# MCU.net
KiCad netlist of a schematic drawn in Altium Designer
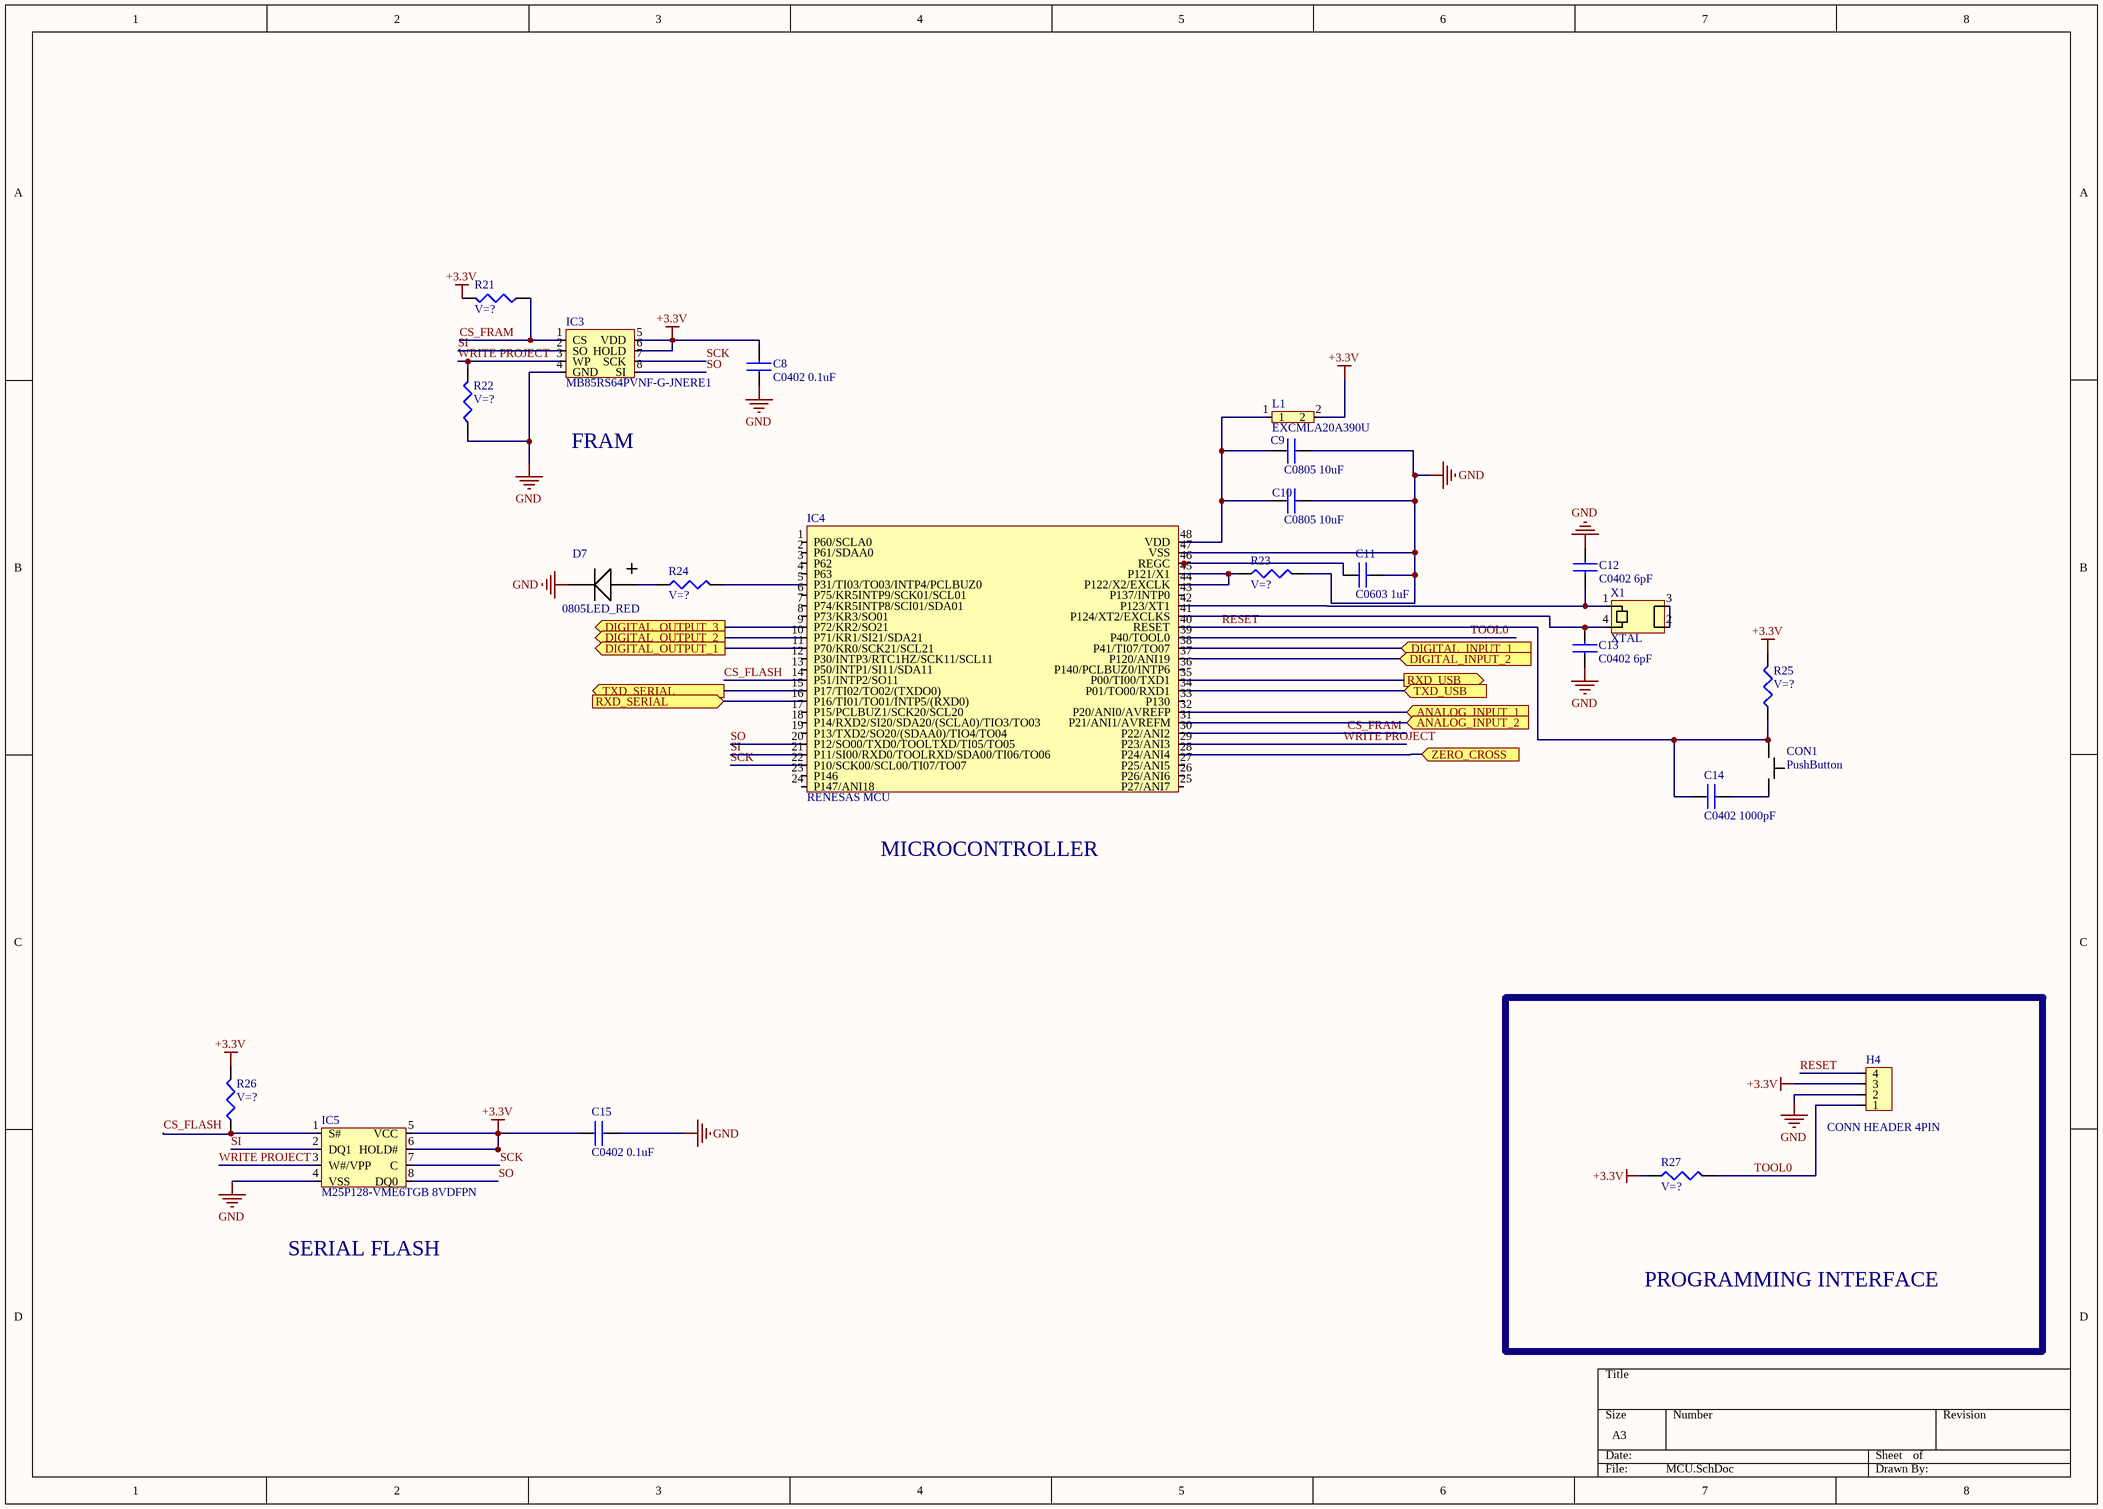
[diagram p0: MCU.SchDoc]

(export (version "E")
  (design (tool "Eeschema 10.0.6"))
  (components
    (comp (ref "C8")
      (value "C0402 0.1uF")
      (footprint "C0402")
      (description "CAP CER 0.1uF 16V X7R 0402 / SAMSUNG")
      (libsource (lib "COOP4403_BerkantAY") (part "C0402 0.1uF"))
    )
    (comp (ref "C9")
      (value "C0805 10uF")
      (footprint "C0805")
      (description "CAP CER 10uF 6.3V X7R 0805 / C0805C106K9RACTU")
      (libsource (lib "COOP4403_BerkantAY") (part "C0805 10uF"))
    )
    (comp (ref "C10")
      (value "C0805 10uF")
      (footprint "C0805")
      (description "CAP CER 10uF 6.3V X7R 0805 / C0805C106K9RACTU")
      (libsource (lib "COOP4403_BerkantAY") (part "C0805 10uF"))
    )
    (comp (ref "C11")
      (value "C0603 1uF")
      (footprint "C0603")
      (description "CAP CER 1uF 10V X7R 0603")
      (libsource (lib "COOP4403_BerkantAY") (part "C0603 1uF"))
    )
    (comp (ref "C12")
      (value "C0402 6pF")
      (footprint "C0402")
      (description "CAP CER 6pF 100V C0G/NP0 0402 / KEMET")
      (libsource (lib "COOP4403_BerkantAY") (part "C0402 6pF"))
    )
    (comp (ref "C13")
      (value "C0402 6pF")
      (footprint "C0402")
      (description "CAP CER 6pF 100V C0G/NP0 0402 / KEMET")
      (libsource (lib "COOP4403_BerkantAY") (part "C0402 6pF"))
    )
    (comp (ref "C14")
      (value "C0402 1000pF")
      (footprint "C0402")
      (description "CAP CER 1000pF 26V X7R 0402 / CL05B102KA5NNNC")
      (libsource (lib "COOP4403_BerkantAY") (part "C0402 1000pF"))
    )
    (comp (ref "C15")
      (value "C0402 0.1uF")
      (footprint "C0402")
      (description "CAP CER 0.1uF 16V X7R 0402 / SAMSUNG")
      (libsource (lib "COOP4403_BerkantAY") (part "C0402 0.1uF"))
    )
    (comp (ref "CON1")
      (value "PushButton")
      (footprint "PUSHBUTTON")
      (description "SKPDACD010")
      (libsource (lib "COOP4403_BerkantAY") (part "PushButton"))
    )
    (comp (ref "D7")
      (value "0805LED_RED")
      (footprint "0805LED_GREEN")
      (description "LSR976")
      (libsource (lib "COOP4403_BerkantAY") (part "0805LED_RED"))
    )
    (comp (ref "H4")
      (value "CONN HEADER 4PIN")
      (footprint "CON HEADER 4PIN")
      (description "B4B-XHALFSN")
      (libsource (lib "COOP4403_BerkantAY") (part "CONN HEADER 4PIN"))
    )
    (comp (ref "IC3")
      (value "MB85RS64PVNF-G-JNERE1")
      (footprint "TSOP127P600X155-8N")
      (description "IC FRAM 64K SPI 20MHZ 8SOP")
      (libsource (lib "COOP4403_BerkantAY") (part "MB85RS64PVNF-G-JNERE1"))
    )
    (comp (ref "IC4")
      (value "RENESAS MCU")
      (footprint "TSQFP50P900X900X160-48N")
      (description "IC MCU 16BIT 32KB FLASH 48LQFP")
      (libsource (lib "COOP4403_BerkantAY") (part "RENESAS MCU"))
    )
    (comp (ref "IC5")
      (value "M25P128-VME6TGB 8VDFPN")
      (footprint "QFN127P800X600X85_HS-9N")
      (description "IC FLASH 128M SPI 54MHZ 9VDFPN")
      (libsource (lib "COOP4403_BerkantAY") (part "M25P128-VME6TGB 8VDFPN"))
    )
    (comp (ref "L1")
      (value "EXCMLA20A390U")
      (footprint "L0805")
      (description "FERRITE BEAD 39 OHM")
      (libsource (lib "COOP4403_BerkantAY") (part "EXCMLA20A390U"))
    )
    (comp (ref "R21")
      (value "V=?")
      (footprint "r0402")
      (description "RESISTOR")
      (libsource (lib "COOP4403_BerkantAY") (part "R0402"))
    )
    (comp (ref "R22")
      (value "V=?")
      (footprint "r0402")
      (description "RESISTOR")
      (libsource (lib "COOP4403_BerkantAY") (part "R0402"))
    )
    (comp (ref "R23")
      (value "V=?")
      (footprint "r0402")
      (description "RESISTOR")
      (libsource (lib "COOP4403_BerkantAY") (part "R0402"))
    )
    (comp (ref "R24")
      (value "V=?")
      (footprint "r0402")
      (description "RESISTOR")
      (libsource (lib "COOP4403_BerkantAY") (part "R0402"))
    )
    (comp (ref "R25")
      (value "V=?")
      (footprint "r0402")
      (description "RESISTOR")
      (libsource (lib "COOP4403_BerkantAY") (part "R0402"))
    )
    (comp (ref "R26")
      (value "V=?")
      (footprint "r0402")
      (description "RESISTOR")
      (libsource (lib "COOP4403_BerkantAY") (part "R0402"))
    )
    (comp (ref "R27")
      (value "V=?")
      (footprint "r0402")
      (description "RESISTOR")
      (libsource (lib "COOP4403_BerkantAY") (part "R0402"))
    )
    (comp (ref "X1")
      (value "XTAL")
      (footprint "XTAL")
      (description "SSP-T7-F")
      (libsource (lib "COOP4403_BerkantAY") (part "XTAL"))
    )
  )
  (nets
    (net (code "1") (name "+3.3V") (class "Default")
      (node (ref "C15") (pin "1") (pinfunction "1_1") (pintype "passive"))
      (node (ref "C8") (pin "2") (pinfunction "2_2") (pintype "passive"))
      (node (ref "H4") (pin "3") (pinfunction "3_3") (pintype "passive"))
      (node (ref "IC3") (pin "5") (pinfunction "VDD_5") (pintype "passive"))
      (node (ref "IC3") (pin "6") (pinfunction "HOLD_6") (pintype "passive"))
      (node (ref "IC5") (pin "5") (pinfunction "VCC_5") (pintype "passive"))
      (node (ref "IC5") (pin "6") (pinfunction "HOLD#_6") (pintype "passive"))
      (node (ref "L1") (pin "2") (pinfunction "2_2") (pintype "passive"))
      (node (ref "R21") (pin "2") (pinfunction "2_2") (pintype "passive"))
      (node (ref "R25") (pin "2") (pinfunction "2_2") (pintype "passive"))
      (node (ref "R26") (pin "2") (pinfunction "2_2") (pintype "passive"))
      (node (ref "R27") (pin "1") (pinfunction "1_1") (pintype "passive"))
    )
    (net (code "2") (name "/ANALOG_INPUT_1") (class "Default")
      (node (ref "IC4") (pin "32") (pinfunction "P20/ANI0/AVREFP_32") (pintype "passive"))
    )
    (net (code "3") (name "/ANALOG_INPUT_2") (class "Default")
      (node (ref "IC4") (pin "31") (pinfunction "P21/ANI1/AVREFM_31") (pintype "passive"))
    )
    (net (code "4") (name "/CS_FLASH") (class "Default")
      (node (ref "IC4") (pin "14") (pinfunction "P51/INTP2/SO11_14") (pintype "passive"))
      (node (ref "IC5") (pin "1") (pinfunction "S#_1") (pintype "passive"))
      (node (ref "R26") (pin "1") (pinfunction "1_1") (pintype "passive"))
    )
    (net (code "5") (name "/CS_FRAM") (class "Default")
      (node (ref "IC3") (pin "1") (pinfunction "CS_1") (pintype "passive"))
      (node (ref "IC4") (pin "30") (pinfunction "P22/ANI2_30") (pintype "passive"))
      (node (ref "R21") (pin "1") (pinfunction "1_1") (pintype "passive"))
    )
    (net (code "6") (name "/DIGITAL_INPUT_1") (class "Default")
      (node (ref "IC4") (pin "38") (pinfunction "P41/TI07/TO07_38") (pintype "passive"))
    )
    (net (code "7") (name "/DIGITAL_INPUT_2") (class "Default")
      (node (ref "IC4") (pin "37") (pinfunction "P120/ANI19_37") (pintype "passive"))
    )
    (net (code "8") (name "/DIGITAL_OUTPUT_1") (class "Default")
      (node (ref "IC4") (pin "11") (pinfunction "P70/KR0/SCK21/SCL21_11") (pintype "passive"))
    )
    (net (code "9") (name "/DIGITAL_OUTPUT_2") (class "Default")
      (node (ref "IC4") (pin "10") (pinfunction "P71/KR1/SI21/SDA21_10") (pintype "passive"))
    )
    (net (code "10") (name "/DIGITAL_OUTPUT_3") (class "Default")
      (node (ref "IC4") (pin "9") (pinfunction "P72/KR2/SO21_9") (pintype "passive"))
    )
    (net (code "11") (name "/RESET") (class "Default")
      (node (ref "C14") (pin "1") (pinfunction "1_1") (pintype "passive"))
      (node (ref "CON1") (pin "1") (pinfunction "1_1") (pintype "passive"))
      (node (ref "H4") (pin "4") (pinfunction "4_4") (pintype "passive"))
      (node (ref "IC4") (pin "40") (pinfunction "RESET_40") (pintype "passive"))
      (node (ref "R25") (pin "1") (pinfunction "1_1") (pintype "passive"))
    )
    (net (code "12") (name "/RXD_SERIAL") (class "Default")
      (node (ref "IC4") (pin "16") (pinfunction "P16/TI01/TO01/INTP5/(RXD0)_16") (pintype "passive"))
    )
    (net (code "13") (name "/RXD_USB") (class "Default")
      (node (ref "IC4") (pin "35") (pinfunction "P00/TI00/TXD1_35") (pintype "passive"))
    )
    (net (code "14") (name "/SCK") (class "Default")
      (node (ref "IC3") (pin "7") (pinfunction "SCK_7") (pintype "passive"))
      (node (ref "IC4") (pin "22") (pinfunction "P10/SCK00/SCL00/TI07/TO07_22") (pintype "passive"))
      (node (ref "IC5") (pin "7") (pinfunction "C_7") (pintype "passive"))
    )
    (net (code "15") (name "/SI") (class "Default")
      (node (ref "IC3") (pin "2") (pinfunction "SO_2") (pintype "passive"))
      (node (ref "IC4") (pin "21") (pinfunction "P11/SI00/RXD0/TOOLRXD/SDA00/TI06/TO06_21") (pintype "passive"))
      (node (ref "IC5") (pin "2") (pinfunction "DQ1_2") (pintype "passive"))
    )
    (net (code "16") (name "/SO") (class "Default")
      (node (ref "IC3") (pin "8") (pinfunction "SI_8") (pintype "passive"))
      (node (ref "IC4") (pin "20") (pinfunction "P12/SO00/TXD0/TOOLTXD/TI05/TO05_20") (pintype "passive"))
      (node (ref "IC5") (pin "8") (pinfunction "DQ0_8") (pintype "passive"))
    )
    (net (code "17") (name "/TOOL0") (class "Default")
      (node (ref "H4") (pin "1") (pinfunction "1_1") (pintype "passive"))
      (node (ref "IC4") (pin "39") (pinfunction "P40/TOOL0_39") (pintype "passive"))
      (node (ref "R27") (pin "2") (pinfunction "2_2") (pintype "passive"))
    )
    (net (code "18") (name "/TXD_SERIAL") (class "Default")
      (node (ref "IC4") (pin "15") (pinfunction "P17/TI02/TO02/(TXDO0)_15") (pintype "passive"))
    )
    (net (code "19") (name "/TXD_USB") (class "Default")
      (node (ref "IC4") (pin "34") (pinfunction "P01/TO00/RXD1_34") (pintype "passive"))
    )
    (net (code "20") (name "/WRITE PROJECT") (class "Default")
      (node (ref "IC3") (pin "3") (pinfunction "WP_3") (pintype "passive"))
      (node (ref "IC4") (pin "29") (pinfunction "P23/ANI3_29") (pintype "passive"))
      (node (ref "IC5") (pin "3") (pinfunction "W#/VPP_3") (pintype "passive"))
      (node (ref "R22") (pin "2") (pinfunction "2_2") (pintype "passive"))
    )
    (net (code "21") (name "/ZERO_CROSS") (class "Default")
      (node (ref "IC4") (pin "28") (pinfunction "P24/ANI4_28") (pintype "passive"))
    )
    (net (code "22") (name "GND") (class "Default")
      (node (ref "C10") (pin "2") (pinfunction "2_2") (pintype "passive"))
      (node (ref "C11") (pin "2") (pinfunction "2_2") (pintype "passive"))
      (node (ref "C12") (pin "1") (pinfunction "1_1") (pintype "passive"))
      (node (ref "C13") (pin "1") (pinfunction "1_1") (pintype "passive"))
      (node (ref "C15") (pin "2") (pinfunction "2_2") (pintype "passive"))
      (node (ref "C8") (pin "1") (pinfunction "1_1") (pintype "passive"))
      (node (ref "C9") (pin "2") (pinfunction "2_2") (pintype "passive"))
      (node (ref "D7") (pin "1") (pinfunction "1_1") (pintype "passive"))
      (node (ref "H4") (pin "2") (pinfunction "2_2") (pintype "passive"))
      (node (ref "IC3") (pin "4") (pinfunction "GND_4") (pintype "passive"))
      (node (ref "IC4") (pin "47") (pinfunction "VSS_47") (pintype "passive"))
      (node (ref "IC5") (pin "4") (pinfunction "VSS_4") (pintype "passive"))
      (node (ref "R22") (pin "1") (pinfunction "1_1") (pintype "passive"))
      (node (ref "R23") (pin "2") (pinfunction "2_2") (pintype "passive"))
    )
    (net (code "23") (name "Net-(C14-Pad2)") (class "Default")
      (node (ref "C14") (pin "2") (pinfunction "2_2") (pintype "passive"))
      (node (ref "CON1") (pin "2") (pinfunction "2_2") (pintype "passive"))
    )
    (net (code "24") (name "Net-(D7-Pad2)") (class "Default")
      (node (ref "D7") (pin "2") (pinfunction "2_2") (pintype "passive"))
      (node (ref "R24") (pin "1") (pinfunction "1_1") (pintype "passive"))
    )
    (net (code "25") (name "Net-(IC4-P31{slash}TI03{slash}TO03{slash}INTP4{slash}PCLBUZ0)") (class "Default")
      (node (ref "IC4") (pin "5") (pinfunction "P31/TI03/TO03/INTP4/PCLBUZ0_5") (pintype "passive"))
      (node (ref "R24") (pin "2") (pinfunction "2_2") (pintype "passive"))
    )
    (net (code "26") (name "Net-(IC4-P121{slash}X1)") (class "Default")
      (node (ref "IC4") (pin "44") (pinfunction "P122/X2/EXCLK_44") (pintype "passive"))
      (node (ref "IC4") (pin "45") (pinfunction "P121/X1_45") (pintype "passive"))
      (node (ref "R23") (pin "1") (pinfunction "1_1") (pintype "passive"))
    )
    (net (code "27") (name "Net-(IC4-P123{slash}XT1)") (class "Default")
      (node (ref "C12") (pin "2") (pinfunction "2_2") (pintype "passive"))
      (node (ref "IC4") (pin "42") (pinfunction "P123/XT1_42") (pintype "passive"))
      (node (ref "X1") (pin "1") (pinfunction "1_1") (pintype "passive"))
    )
    (net (code "28") (name "Net-(IC4-P124{slash}XT2{slash}EXCLKS)") (class "Default")
      (node (ref "C13") (pin "2") (pinfunction "2_2") (pintype "passive"))
      (node (ref "IC4") (pin "41") (pinfunction "P124/XT2/EXCLKS_41") (pintype "passive"))
      (node (ref "X1") (pin "4") (pinfunction "4_4") (pintype "passive"))
    )
    (net (code "29") (name "Net-(IC4-REGC)") (class "Default")
      (node (ref "C11") (pin "1") (pinfunction "1_1") (pintype "passive"))
      (node (ref "IC4") (pin "46") (pinfunction "REGC_46") (pintype "passive"))
    )
    (net (code "30") (name "Net-(IC4-VDD)") (class "Default")
      (node (ref "C10") (pin "1") (pinfunction "1_1") (pintype "passive"))
      (node (ref "C9") (pin "1") (pinfunction "1_1") (pintype "passive"))
      (node (ref "IC4") (pin "48") (pinfunction "VDD_48") (pintype "passive"))
      (node (ref "L1") (pin "1") (pinfunction "1_1") (pintype "passive"))
    )
    (net (code "31") (name "Net-(X1-Pad2)") (class "Default")
      (node (ref "X1") (pin "2") (pinfunction "2_2") (pintype "passive"))
      (node (ref "X1") (pin "3") (pinfunction "3_3") (pintype "passive"))
    )
    (net (code "32") (name "unconnected-(IC4-P13{slash}TXD2{slash}SO20{slash}(SDAA0){slash}TIO4{slash}TO04-Pad19)") (class "Default")
      (node (ref "IC4") (pin "19") (pinfunction "P13/TXD2/SO20/(SDAA0)/TIO4/TO04_19") (pintype "passive"))
    )
    (net (code "33") (name "unconnected-(IC4-P14{slash}RXD2{slash}SI20{slash}SDA20{slash}(SCLA0){slash}TIO3{slash}TO03-Pad18)") (class "Default")
      (node (ref "IC4") (pin "18") (pinfunction "P14/RXD2/SI20/SDA20/(SCLA0)/TIO3/TO03_18") (pintype "passive"))
    )
    (net (code "34") (name "unconnected-(IC4-P15{slash}PCLBUZ1{slash}SCK20{slash}SCL20-Pad17)") (class "Default")
      (node (ref "IC4") (pin "17") (pinfunction "P15/PCLBUZ1/SCK20/SCL20_17") (pintype "passive"))
    )
    (net (code "35") (name "unconnected-(IC4-P25{slash}ANI5-Pad27)") (class "Default")
      (node (ref "IC4") (pin "27") (pinfunction "P25/ANI5_27") (pintype "passive"))
    )
    (net (code "36") (name "unconnected-(IC4-P26{slash}ANI6-Pad26)") (class "Default")
      (node (ref "IC4") (pin "26") (pinfunction "P26/ANI6_26") (pintype "passive"))
    )
    (net (code "37") (name "unconnected-(IC4-P27{slash}ANI7-Pad25)") (class "Default")
      (node (ref "IC4") (pin "25") (pinfunction "P27/ANI7_25") (pintype "passive"))
    )
    (net (code "38") (name "unconnected-(IC4-P30{slash}INTP3{slash}RTC1HZ{slash}SCK11{slash}SCL11-Pad12)") (class "Default")
      (node (ref "IC4") (pin "12") (pinfunction "P30/INTP3/RTC1HZ/SCK11/SCL11_12") (pintype "passive"))
    )
    (net (code "39") (name "unconnected-(IC4-P50{slash}INTP1{slash}SI11{slash}SDA11-Pad13)") (class "Default")
      (node (ref "IC4") (pin "13") (pinfunction "P50/INTP1/SI11/SDA11_13") (pintype "passive"))
    )
    (net (code "40") (name "unconnected-(IC4-P60{slash}SCLA0-Pad1)") (class "Default")
      (node (ref "IC4") (pin "1") (pinfunction "P60/SCLA0_1") (pintype "passive"))
    )
    (net (code "41") (name "unconnected-(IC4-P61{slash}SDAA0-Pad2)") (class "Default")
      (node (ref "IC4") (pin "2") (pinfunction "P61/SDAA0_2") (pintype "passive"))
    )
    (net (code "42") (name "unconnected-(IC4-P62-Pad3)") (class "Default")
      (node (ref "IC4") (pin "3") (pinfunction "P62_3") (pintype "passive"))
    )
    (net (code "43") (name "unconnected-(IC4-P63-Pad4)") (class "Default")
      (node (ref "IC4") (pin "4") (pinfunction "P63_4") (pintype "passive"))
    )
    (net (code "44") (name "unconnected-(IC4-P73{slash}KR3{slash}SO01-Pad8)") (class "Default")
      (node (ref "IC4") (pin "8") (pinfunction "P73/KR3/SO01_8") (pintype "passive"))
    )
    (net (code "45") (name "unconnected-(IC4-P74{slash}KR5INTP8{slash}SCI01{slash}SDA01-Pad7)") (class "Default")
      (node (ref "IC4") (pin "7") (pinfunction "P74/KR5INTP8/SCI01/SDA01_7") (pintype "passive"))
    )
    (net (code "46") (name "unconnected-(IC4-P75{slash}KR5INTP9{slash}SCK01{slash}SCL01-Pad6)") (class "Default")
      (node (ref "IC4") (pin "6") (pinfunction "P75/KR5INTP9/SCK01/SCL01_6") (pintype "passive"))
    )
    (net (code "47") (name "unconnected-(IC4-P130-Pad33)") (class "Default")
      (node (ref "IC4") (pin "33") (pinfunction "P130_33") (pintype "passive"))
    )
    (net (code "48") (name "unconnected-(IC4-P137{slash}INTP0-Pad43)") (class "Default")
      (node (ref "IC4") (pin "43") (pinfunction "P137/INTP0_43") (pintype "passive"))
    )
    (net (code "49") (name "unconnected-(IC4-P140{slash}PCLBUZ0{slash}INTP6-Pad36)") (class "Default")
      (node (ref "IC4") (pin "36") (pinfunction "P140/PCLBUZ0/INTP6_36") (pintype "passive"))
    )
    (net (code "50") (name "unconnected-(IC4-P146-Pad23)") (class "Default")
      (node (ref "IC4") (pin "23") (pinfunction "P146_23") (pintype "passive"))
    )
    (net (code "51") (name "unconnected-(IC4-P147{slash}ANI18-Pad24)") (class "Default")
      (node (ref "IC4") (pin "24") (pinfunction "P147/ANI18_24") (pintype "passive"))
    )
  )
)
